# S7CAS-PLEIADES-CARTE-MERE_Pxx_FPGA_bank3.net
KiCad netlist of a schematic drawn in Altium Designer
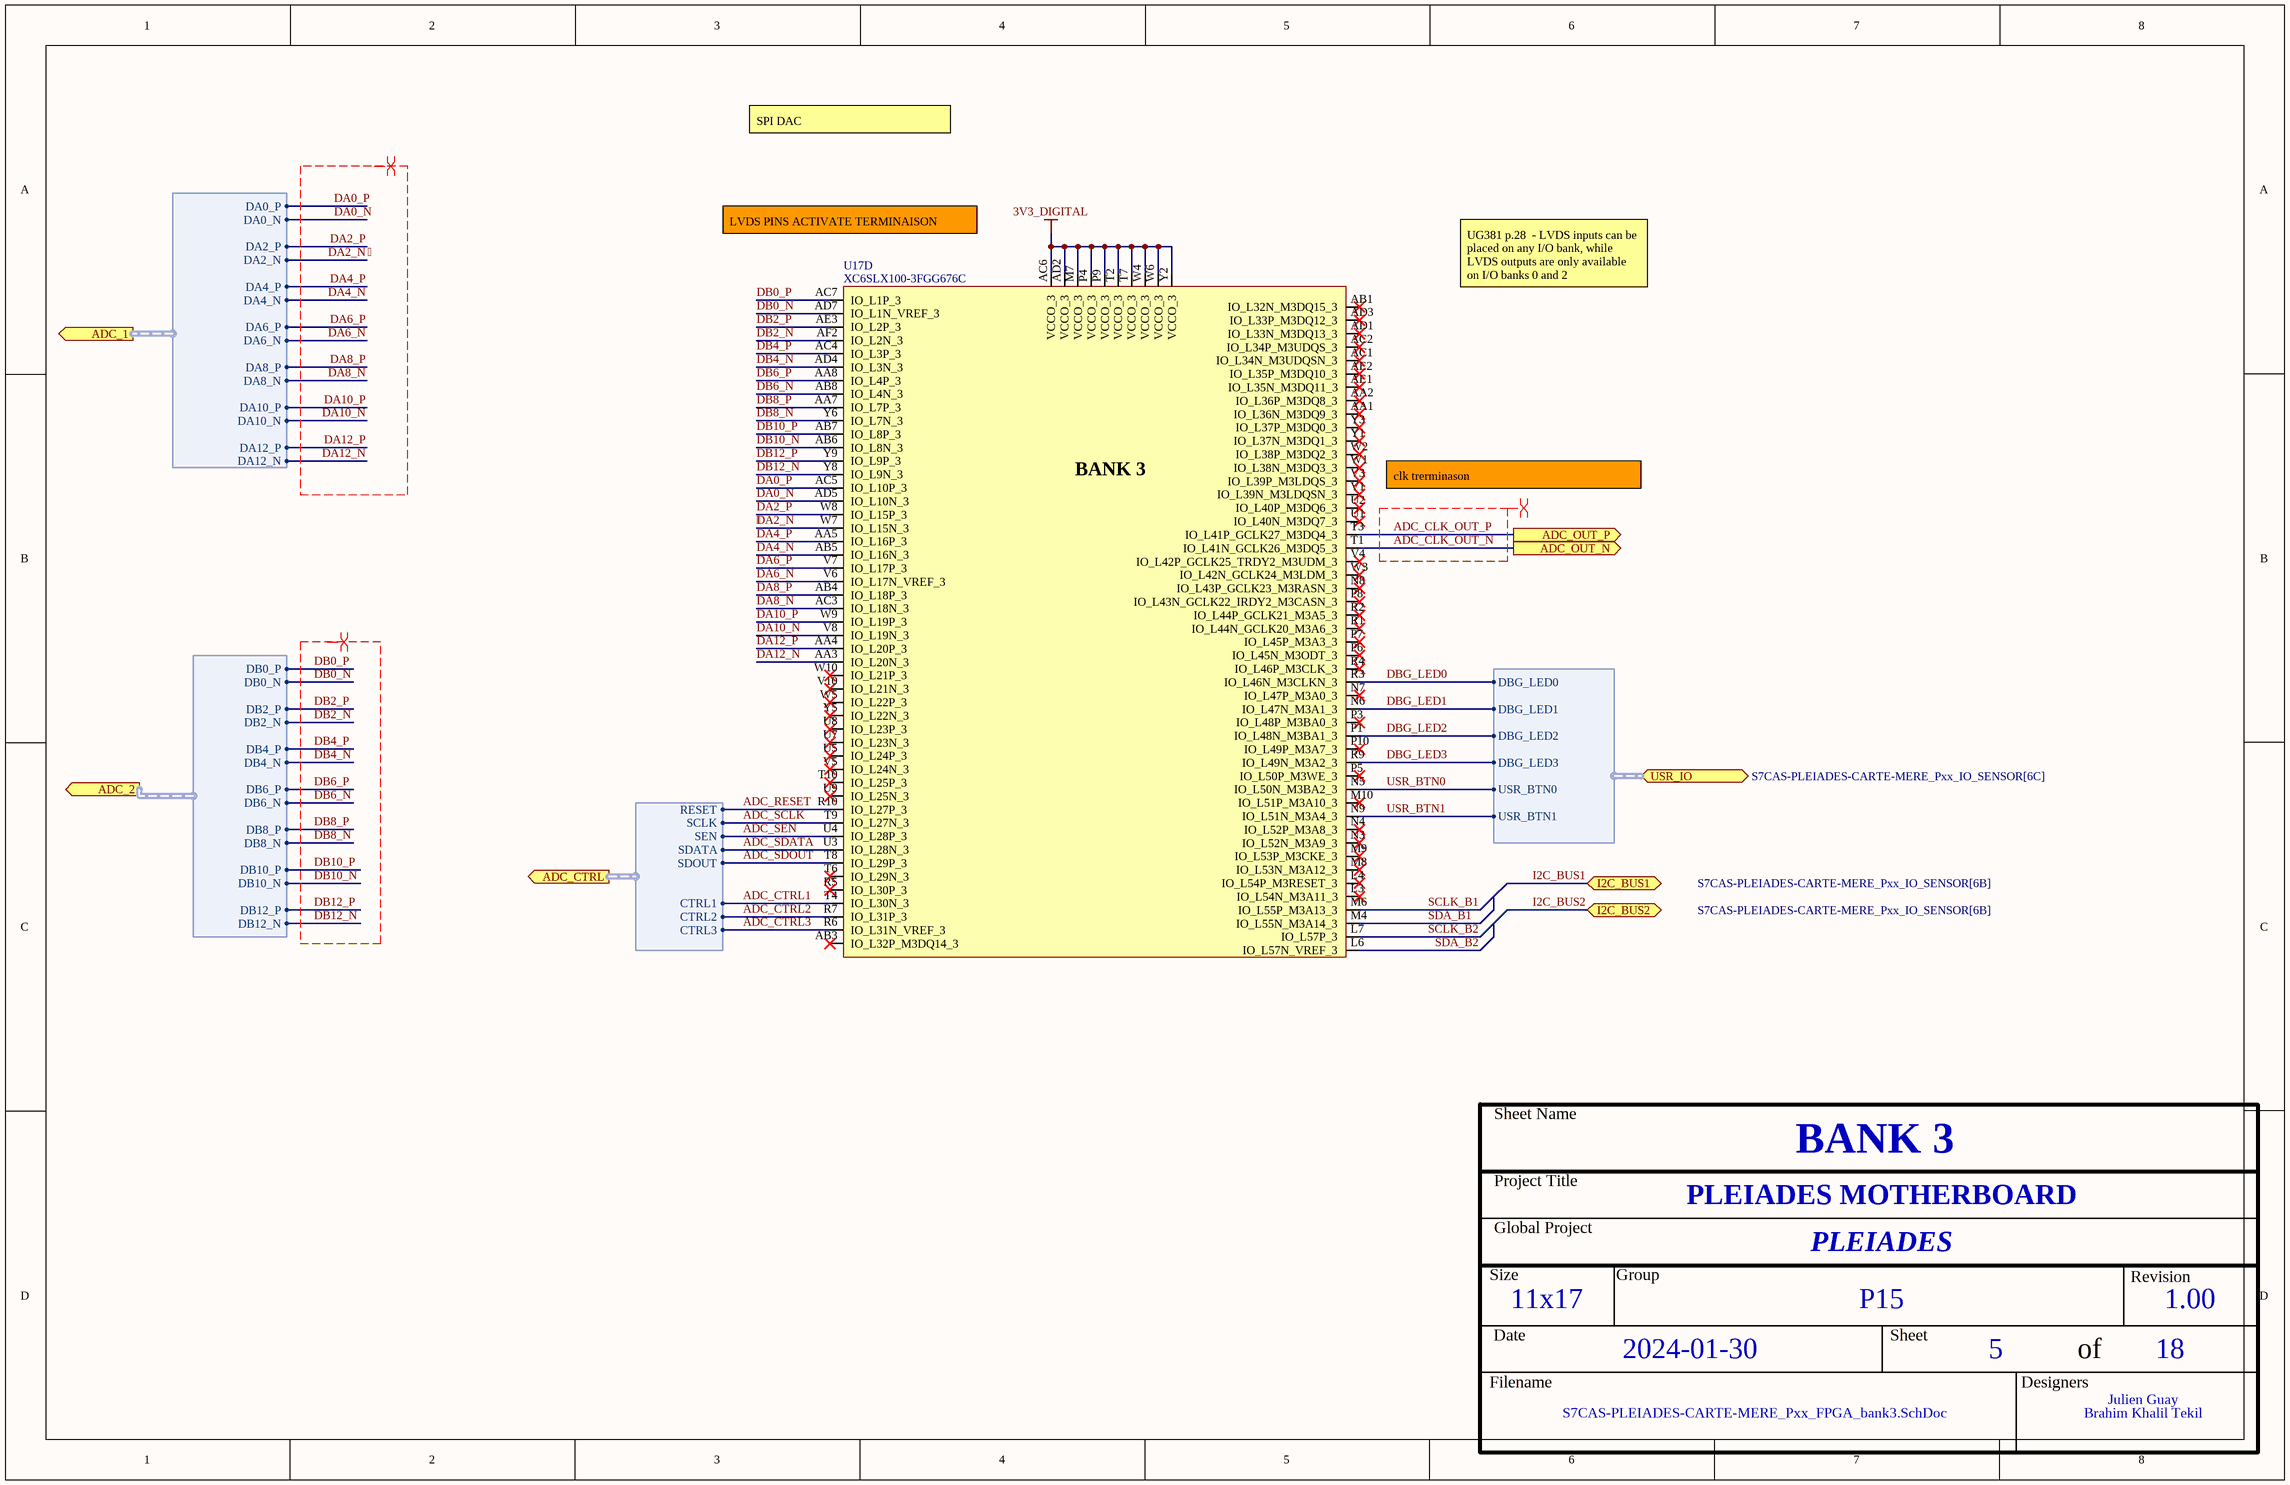
[diagram p0: S7CAS-PLEIADES-CARTE-MERE_Pxx_FPGA_bank3.SchDoc]

(export (version "E")
  (design (tool "Eeschema 10.0.6"))
  (components
    (comp (ref "U17")
      (value "XC6SLX100-3FGG676C")
      (footprint "FPGA_XILINX_FGG676")
      (description "FPGA - XILINX SPARTAN 6 480 I/O - BGA-676")
      (fields
        (field (name "VOLTAGE") "1.14 V ~ 1.26 V")
        (field (name "MFG") "Xilinx")
        (field (name "CREATEDBY") "Jonathan Bouchard")
      )
      (libsource (lib "S7CAS_LIB2023") (part "FPGA_XC6SLX100-3FGG676C"))
    )
  )
  (nets
    (net (code "7") (name "/") (class "Default")
      (node (ref "U17") (pin "W7") (pinfunction "IO_L15N_3_W7") (pintype "passive"))
    )
    (net (code "8") (name "/ADC_CLK_OUT_N") (class "Default")
      (node (ref "U17") (pin "T1") (pinfunction "IO_L41N_GCLK26_M3DQ5_3_T1") (pintype "passive"))
    )
    (net (code "9") (name "/ADC_CLK_OUT_P") (class "Default")
      (node (ref "U17") (pin "T3") (pinfunction "IO_L41P_GCLK27_M3DQ4_3_T3") (pintype "passive"))
    )
    (net (code "10") (name "/ADC_CTRL1") (class "Default")
      (node (ref "U17") (pin "T4") (pinfunction "IO_L30N_3_T4") (pintype "passive"))
    )
    (net (code "11") (name "/ADC_CTRL2") (class "Default")
      (node (ref "U17") (pin "R7") (pinfunction "IO_L31P_3_R7") (pintype "passive"))
    )
    (net (code "12") (name "/ADC_CTRL3") (class "Default")
      (node (ref "U17") (pin "R6") (pinfunction "IO_L31N_VREF_3_R6") (pintype "passive"))
    )
    (net (code "13") (name "/ADC_RESET") (class "Default")
      (node (ref "U17") (pin "R10") (pinfunction "IO_L27P_3_R10") (pintype "passive"))
    )
    (net (code "14") (name "/ADC_SCLK") (class "Default")
      (node (ref "U17") (pin "T9") (pinfunction "IO_L27N_3_T9") (pintype "passive"))
    )
    (net (code "15") (name "/ADC_SDATA") (class "Default")
      (node (ref "U17") (pin "U3") (pinfunction "IO_L28N_3_U3") (pintype "passive"))
    )
    (net (code "16") (name "/ADC_SDOUT") (class "Default")
      (node (ref "U17") (pin "T8") (pinfunction "IO_L29P_3_T8") (pintype "passive"))
    )
    (net (code "17") (name "/ADC_SEN") (class "Default")
      (node (ref "U17") (pin "U4") (pinfunction "IO_L28P_3_U4") (pintype "passive"))
    )
    (net (code "18") (name "/DA0_N") (class "Default")
      (node (ref "U17") (pin "AD5") (pinfunction "IO_L10N_3_AD5") (pintype "passive"))
    )
    (net (code "19") (name "/DA0_P") (class "Default")
      (node (ref "U17") (pin "AC5") (pinfunction "IO_L10P_3_AC5") (pintype "passive"))
    )
    (net (code "20") (name "/DA2_P") (class "Default")
      (node (ref "U17") (pin "W8") (pinfunction "IO_L15P_3_W8") (pintype "passive"))
    )
    (net (code "21") (name "/DA4_N") (class "Default")
      (node (ref "U17") (pin "AB5") (pinfunction "IO_L16N_3_AB5") (pintype "passive"))
    )
    (net (code "22") (name "/DA4_P") (class "Default")
      (node (ref "U17") (pin "AA5") (pinfunction "IO_L16P_3_AA5") (pintype "passive"))
    )
    (net (code "23") (name "/DA6_N") (class "Default")
      (node (ref "U17") (pin "V6") (pinfunction "IO_L17N_VREF_3_V6") (pintype "passive"))
    )
    (net (code "24") (name "/DA6_P") (class "Default")
      (node (ref "U17") (pin "V7") (pinfunction "IO_L17P_3_V7") (pintype "passive"))
    )
    (net (code "25") (name "/DA8_N") (class "Default")
      (node (ref "U17") (pin "AC3") (pinfunction "IO_L18N_3_AC3") (pintype "passive"))
    )
    (net (code "26") (name "/DA8_P") (class "Default")
      (node (ref "U17") (pin "AB4") (pinfunction "IO_L18P_3_AB4") (pintype "passive"))
    )
    (net (code "27") (name "/DA10_N") (class "Default")
      (node (ref "U17") (pin "V8") (pinfunction "IO_L19N_3_V8") (pintype "passive"))
    )
    (net (code "28") (name "/DA10_P") (class "Default")
      (node (ref "U17") (pin "W9") (pinfunction "IO_L19P_3_W9") (pintype "passive"))
    )
    (net (code "29") (name "/DA12_N") (class "Default")
      (node (ref "U17") (pin "AA3") (pinfunction "IO_L20N_3_AA3") (pintype "passive"))
    )
    (net (code "30") (name "/DA12_P") (class "Default")
      (node (ref "U17") (pin "AA4") (pinfunction "IO_L20P_3_AA4") (pintype "passive"))
    )
    (net (code "31") (name "/DB0_N") (class "Default")
      (node (ref "U17") (pin "AD7") (pinfunction "IO_L1N_VREF_3_AD7") (pintype "passive"))
    )
    (net (code "32") (name "/DB0_P") (class "Default")
      (node (ref "U17") (pin "AC7") (pinfunction "IO_L1P_3_AC7") (pintype "passive"))
    )
    (net (code "33") (name "/DB2_N") (class "Default")
      (node (ref "U17") (pin "AF2") (pinfunction "IO_L2N_3_AF2") (pintype "passive"))
    )
    (net (code "34") (name "/DB2_P") (class "Default")
      (node (ref "U17") (pin "AE3") (pinfunction "IO_L2P_3_AE3") (pintype "passive"))
    )
    (net (code "35") (name "/DB4_N") (class "Default")
      (node (ref "U17") (pin "AD4") (pinfunction "IO_L3N_3_AD4") (pintype "passive"))
    )
    (net (code "36") (name "/DB4_P") (class "Default")
      (node (ref "U17") (pin "AC4") (pinfunction "IO_L3P_3_AC4") (pintype "passive"))
    )
    (net (code "37") (name "/DB6_N") (class "Default")
      (node (ref "U17") (pin "AB8") (pinfunction "IO_L4N_3_AB8") (pintype "passive"))
    )
    (net (code "38") (name "/DB6_P") (class "Default")
      (node (ref "U17") (pin "AA8") (pinfunction "IO_L4P_3_AA8") (pintype "passive"))
    )
    (net (code "39") (name "/DB8_N") (class "Default")
      (node (ref "U17") (pin "Y6") (pinfunction "IO_L7N_3_Y6") (pintype "passive"))
    )
    (net (code "40") (name "/DB8_P") (class "Default")
      (node (ref "U17") (pin "AA7") (pinfunction "IO_L7P_3_AA7") (pintype "passive"))
    )
    (net (code "41") (name "/DB10_N") (class "Default")
      (node (ref "U17") (pin "AB6") (pinfunction "IO_L8N_3_AB6") (pintype "passive"))
    )
    (net (code "42") (name "/DB10_P") (class "Default")
      (node (ref "U17") (pin "AB7") (pinfunction "IO_L8P_3_AB7") (pintype "passive"))
    )
    (net (code "43") (name "/DB12_N") (class "Default")
      (node (ref "U17") (pin "Y8") (pinfunction "IO_L9N_3_Y8") (pintype "passive"))
    )
    (net (code "44") (name "/DB12_P") (class "Default")
      (node (ref "U17") (pin "Y9") (pinfunction "IO_L9P_3_Y9") (pintype "passive"))
    )
    (net (code "45") (name "/DBG_LED0") (class "Default")
      (node (ref "U17") (pin "R3") (pinfunction "IO_L46N_M3CLKN_3_R3") (pintype "passive"))
    )
    (net (code "46") (name "/DBG_LED1") (class "Default")
      (node (ref "U17") (pin "N6") (pinfunction "IO_L47N_M3A1_3_N6") (pintype "passive"))
    )
    (net (code "47") (name "/DBG_LED2") (class "Default")
      (node (ref "U17") (pin "P1") (pinfunction "IO_L48N_M3BA1_3_P1") (pintype "passive"))
    )
    (net (code "48") (name "/DBG_LED3") (class "Default")
      (node (ref "U17") (pin "R9") (pinfunction "IO_L49N_M3A2_3_R9") (pintype "passive"))
    )
    (net (code "49") (name "/SCLK_B1") (class "Default")
      (node (ref "U17") (pin "M6") (pinfunction "IO_L55P_M3A13_3_M6") (pintype "passive"))
    )
    (net (code "50") (name "/SCLK_B2") (class "Default")
      (node (ref "U17") (pin "L7") (pinfunction "IO_L57P_3_L7") (pintype "passive"))
    )
    (net (code "51") (name "/SDA_B1") (class "Default")
      (node (ref "U17") (pin "M4") (pinfunction "IO_L55N_M3A14_3_M4") (pintype "passive"))
    )
    (net (code "52") (name "/SDA_B2") (class "Default")
      (node (ref "U17") (pin "L6") (pinfunction "IO_L57N_VREF_3_L6") (pintype "passive"))
    )
    (net (code "53") (name "/USR_BTN0") (class "Default")
      (node (ref "U17") (pin "N5") (pinfunction "IO_L50N_M3BA2_3_N5") (pintype "passive"))
    )
    (net (code "54") (name "/USR_BTN1") (class "Default")
      (node (ref "U17") (pin "N9") (pinfunction "IO_L51N_M3A4_3_N9") (pintype "passive"))
    )
    (net (code "61") (name "3V3_DIGITAL") (class "Default")
      (node (ref "U17") (pin "AC6") (pinfunction "VCCO_3_AC6") (pintype "passive"))
      (node (ref "U17") (pin "AD2") (pinfunction "VCCO_3_AD2") (pintype "passive"))
      (node (ref "U17") (pin "M7") (pinfunction "VCCO_3_M7") (pintype "passive"))
      (node (ref "U17") (pin "P4") (pinfunction "VCCO_3_P4") (pintype "passive"))
      (node (ref "U17") (pin "P9") (pinfunction "VCCO_3_P9") (pintype "passive"))
      (node (ref "U17") (pin "T2") (pinfunction "VCCO_3_T2") (pintype "passive"))
      (node (ref "U17") (pin "T7") (pinfunction "VCCO_3_T7") (pintype "passive"))
      (node (ref "U17") (pin "W4") (pinfunction "VCCO_3_W4") (pintype "passive"))
      (node (ref "U17") (pin "W6") (pinfunction "VCCO_3_W6") (pintype "passive"))
      (node (ref "U17") (pin "Y2") (pinfunction "VCCO_3_Y2") (pintype "passive"))
    )
    (net (code "62") (name "unconnected-(U17D-IO_L21N_3-PadV10)") (class "Default")
      (node (ref "U17") (pin "V10") (pinfunction "IO_L21N_3_V10") (pintype "passive+no_connect"))
    )
    (net (code "63") (name "unconnected-(U17D-IO_L21P_3-PadW10)") (class "Default")
      (node (ref "U17") (pin "W10") (pinfunction "IO_L21P_3_W10") (pintype "passive+no_connect"))
    )
    (net (code "64") (name "unconnected-(U17D-IO_L22N_3-PadY5)") (class "Default")
      (node (ref "U17") (pin "Y5") (pinfunction "IO_L22N_3_Y5") (pintype "passive+no_connect"))
    )
    (net (code "65") (name "unconnected-(U17D-IO_L22P_3-PadW5)") (class "Default")
      (node (ref "U17") (pin "W5") (pinfunction "IO_L22P_3_W5") (pintype "passive+no_connect"))
    )
    (net (code "66") (name "unconnected-(U17D-IO_L23N_3-PadU7)") (class "Default")
      (node (ref "U17") (pin "U7") (pinfunction "IO_L23N_3_U7") (pintype "passive+no_connect"))
    )
    (net (code "67") (name "unconnected-(U17D-IO_L23P_3-PadU8)") (class "Default")
      (node (ref "U17") (pin "U8") (pinfunction "IO_L23P_3_U8") (pintype "passive+no_connect"))
    )
    (net (code "68") (name "unconnected-(U17D-IO_L24N_3-PadV5)") (class "Default")
      (node (ref "U17") (pin "V5") (pinfunction "IO_L24N_3_V5") (pintype "passive+no_connect"))
    )
    (net (code "69") (name "unconnected-(U17D-IO_L24P_3-PadU5)") (class "Default")
      (node (ref "U17") (pin "U5") (pinfunction "IO_L24P_3_U5") (pintype "passive+no_connect"))
    )
    (net (code "70") (name "unconnected-(U17D-IO_L25N_3-PadU9)") (class "Default")
      (node (ref "U17") (pin "U9") (pinfunction "IO_L25N_3_U9") (pintype "passive+no_connect"))
    )
    (net (code "71") (name "unconnected-(U17D-IO_L25P_3-PadT10)") (class "Default")
      (node (ref "U17") (pin "T10") (pinfunction "IO_L25P_3_T10") (pintype "passive+no_connect"))
    )
    (net (code "72") (name "unconnected-(U17D-IO_L29N_3-PadT6)") (class "Default")
      (node (ref "U17") (pin "T6") (pinfunction "IO_L29N_3_T6") (pintype "passive+no_connect"))
    )
    (net (code "73") (name "unconnected-(U17D-IO_L30P_3-PadR5)") (class "Default")
      (node (ref "U17") (pin "R5") (pinfunction "IO_L30P_3_R5") (pintype "passive+no_connect"))
    )
    (net (code "74") (name "unconnected-(U17D-IO_L32N_M3DQ15_3-PadAB1)") (class "Default")
      (node (ref "U17") (pin "AB1") (pinfunction "IO_L32N_M3DQ15_3_AB1") (pintype "passive+no_connect"))
    )
    (net (code "75") (name "unconnected-(U17D-IO_L32P_M3DQ14_3-PadAB3)") (class "Default")
      (node (ref "U17") (pin "AB3") (pinfunction "IO_L32P_M3DQ14_3_AB3") (pintype "passive+no_connect"))
    )
    (net (code "76") (name "unconnected-(U17D-IO_L33N_M3DQ13_3-PadAD1)") (class "Default")
      (node (ref "U17") (pin "AD1") (pinfunction "IO_L33N_M3DQ13_3_AD1") (pintype "passive+no_connect"))
    )
    (net (code "77") (name "unconnected-(U17D-IO_L33P_M3DQ12_3-PadAD3)") (class "Default")
      (node (ref "U17") (pin "AD3") (pinfunction "IO_L33P_M3DQ12_3_AD3") (pintype "passive+no_connect"))
    )
    (net (code "78") (name "unconnected-(U17D-IO_L34N_M3UDQSN_3-PadAC1)") (class "Default")
      (node (ref "U17") (pin "AC1") (pinfunction "IO_L34N_M3UDQSN_3_AC1") (pintype "passive+no_connect"))
    )
    (net (code "79") (name "unconnected-(U17D-IO_L34P_M3UDQS_3-PadAC2)") (class "Default")
      (node (ref "U17") (pin "AC2") (pinfunction "IO_L34P_M3UDQS_3_AC2") (pintype "passive+no_connect"))
    )
    (net (code "80") (name "unconnected-(U17D-IO_L35N_M3DQ11_3-PadAE1)") (class "Default")
      (node (ref "U17") (pin "AE1") (pinfunction "IO_L35N_M3DQ11_3_AE1") (pintype "passive+no_connect"))
    )
    (net (code "81") (name "unconnected-(U17D-IO_L35P_M3DQ10_3-PadAE2)") (class "Default")
      (node (ref "U17") (pin "AE2") (pinfunction "IO_L35P_M3DQ10_3_AE2") (pintype "passive+no_connect"))
    )
    (net (code "82") (name "unconnected-(U17D-IO_L36N_M3DQ9_3-PadAA1)") (class "Default")
      (node (ref "U17") (pin "AA1") (pinfunction "IO_L36N_M3DQ9_3_AA1") (pintype "passive+no_connect"))
    )
    (net (code "83") (name "unconnected-(U17D-IO_L36P_M3DQ8_3-PadAA2)") (class "Default")
      (node (ref "U17") (pin "AA2") (pinfunction "IO_L36P_M3DQ8_3_AA2") (pintype "passive+no_connect"))
    )
    (net (code "84") (name "unconnected-(U17D-IO_L37N_M3DQ1_3-PadY1)") (class "Default")
      (node (ref "U17") (pin "Y1") (pinfunction "IO_L37N_M3DQ1_3_Y1") (pintype "passive+no_connect"))
    )
    (net (code "85") (name "unconnected-(U17D-IO_L37P_M3DQ0_3-PadY3)") (class "Default")
      (node (ref "U17") (pin "Y3") (pinfunction "IO_L37P_M3DQ0_3_Y3") (pintype "passive+no_connect"))
    )
    (net (code "86") (name "unconnected-(U17D-IO_L38N_M3DQ3_3-PadW1)") (class "Default")
      (node (ref "U17") (pin "W1") (pinfunction "IO_L38N_M3DQ3_3_W1") (pintype "passive+no_connect"))
    )
    (net (code "87") (name "unconnected-(U17D-IO_L38P_M3DQ2_3-PadW2)") (class "Default")
      (node (ref "U17") (pin "W2") (pinfunction "IO_L38P_M3DQ2_3_W2") (pintype "passive+no_connect"))
    )
    (net (code "88") (name "unconnected-(U17D-IO_L39N_M3LDQSN_3-PadV1)") (class "Default")
      (node (ref "U17") (pin "V1") (pinfunction "IO_L39N_M3LDQSN_3_V1") (pintype "passive+no_connect"))
    )
    (net (code "89") (name "unconnected-(U17D-IO_L39P_M3LDQS_3-PadV3)") (class "Default")
      (node (ref "U17") (pin "V3") (pinfunction "IO_L39P_M3LDQS_3_V3") (pintype "passive+no_connect"))
    )
    (net (code "90") (name "unconnected-(U17D-IO_L40N_M3DQ7_3-PadU1)") (class "Default")
      (node (ref "U17") (pin "U1") (pinfunction "IO_L40N_M3DQ7_3_U1") (pintype "passive+no_connect"))
    )
    (net (code "91") (name "unconnected-(U17D-IO_L40P_M3DQ6_3-PadU2)") (class "Default")
      (node (ref "U17") (pin "U2") (pinfunction "IO_L40P_M3DQ6_3_U2") (pintype "passive+no_connect"))
    )
    (net (code "92") (name "unconnected-(U17D-IO_L42N_GCLK24_M3LDM_3-PadW3)") (class "Default")
      (node (ref "U17") (pin "W3") (pinfunction "IO_L42N_GCLK24_M3LDM_3_W3") (pintype "passive+no_connect"))
    )
    (net (code "93") (name "unconnected-(U17D-IO_L42P_GCLK25_TRDY2_M3UDM_3-PadV4)") (class "Default")
      (node (ref "U17") (pin "V4") (pinfunction "IO_L42P_GCLK25_TRDY2_M3UDM_3_V4") (pintype "passive+no_connect"))
    )
    (net (code "94") (name "unconnected-(U17D-IO_L43N_GCLK22_IRDY2_M3CASN_3-PadP8)") (class "Default")
      (node (ref "U17") (pin "P8") (pinfunction "IO_L43N_GCLK22_IRDY2_M3CASN_3_P8") (pintype "passive+no_connect"))
    )
    (net (code "95") (name "unconnected-(U17D-IO_L43P_GCLK23_M3RASN_3-PadN8)") (class "Default")
      (node (ref "U17") (pin "N8") (pinfunction "IO_L43P_GCLK23_M3RASN_3_N8") (pintype "passive+no_connect"))
    )
    (net (code "96") (name "unconnected-(U17D-IO_L44N_GCLK20_M3A6_3-PadR1)") (class "Default")
      (node (ref "U17") (pin "R1") (pinfunction "IO_L44N_GCLK20_M3A6_3_R1") (pintype "passive+no_connect"))
    )
    (net (code "97") (name "unconnected-(U17D-IO_L44P_GCLK21_M3A5_3-PadR2)") (class "Default")
      (node (ref "U17") (pin "R2") (pinfunction "IO_L44P_GCLK21_M3A5_3_R2") (pintype "passive+no_connect"))
    )
    (net (code "98") (name "unconnected-(U17D-IO_L45N_M3ODT_3-PadP6)") (class "Default")
      (node (ref "U17") (pin "P6") (pinfunction "IO_L45N_M3ODT_3_P6") (pintype "passive+no_connect"))
    )
    (net (code "99") (name "unconnected-(U17D-IO_L45P_M3A3_3-PadP7)") (class "Default")
      (node (ref "U17") (pin "P7") (pinfunction "IO_L45P_M3A3_3_P7") (pintype "passive+no_connect"))
    )
    (net (code "100") (name "unconnected-(U17D-IO_L46P_M3CLK_3-PadR4)") (class "Default")
      (node (ref "U17") (pin "R4") (pinfunction "IO_L46P_M3CLK_3_R4") (pintype "passive+no_connect"))
    )
    (net (code "101") (name "unconnected-(U17D-IO_L47P_M3A0_3-PadN7)") (class "Default")
      (node (ref "U17") (pin "N7") (pinfunction "IO_L47P_M3A0_3_N7") (pintype "passive+no_connect"))
    )
    (net (code "102") (name "unconnected-(U17D-IO_L48P_M3BA0_3-PadP3)") (class "Default")
      (node (ref "U17") (pin "P3") (pinfunction "IO_L48P_M3BA0_3_P3") (pintype "passive+no_connect"))
    )
    (net (code "103") (name "unconnected-(U17D-IO_L49P_M3A7_3-PadP10)") (class "Default")
      (node (ref "U17") (pin "P10") (pinfunction "IO_L49P_M3A7_3_P10") (pintype "passive+no_connect"))
    )
    (net (code "104") (name "unconnected-(U17D-IO_L50P_M3WE_3-PadP5)") (class "Default")
      (node (ref "U17") (pin "P5") (pinfunction "IO_L50P_M3WE_3_P5") (pintype "passive+no_connect"))
    )
    (net (code "105") (name "unconnected-(U17D-IO_L51P_M3A10_3-PadM10)") (class "Default")
      (node (ref "U17") (pin "M10") (pinfunction "IO_L51P_M3A10_3_M10") (pintype "passive+no_connect"))
    )
    (net (code "106") (name "unconnected-(U17D-IO_L52N_M3A9_3-PadN3)") (class "Default")
      (node (ref "U17") (pin "N3") (pinfunction "IO_L52N_M3A9_3_N3") (pintype "passive+no_connect"))
    )
    (net (code "107") (name "unconnected-(U17D-IO_L52P_M3A8_3-PadN4)") (class "Default")
      (node (ref "U17") (pin "N4") (pinfunction "IO_L52P_M3A8_3_N4") (pintype "passive+no_connect"))
    )
    (net (code "108") (name "unconnected-(U17D-IO_L53N_M3A12_3-PadM8)") (class "Default")
      (node (ref "U17") (pin "M8") (pinfunction "IO_L53N_M3A12_3_M8") (pintype "passive+no_connect"))
    )
    (net (code "109") (name "unconnected-(U17D-IO_L53P_M3CKE_3-PadM9)") (class "Default")
      (node (ref "U17") (pin "M9") (pinfunction "IO_L53P_M3CKE_3_M9") (pintype "passive+no_connect"))
    )
    (net (code "110") (name "unconnected-(U17D-IO_L54N_M3A11_3-PadL3)") (class "Default")
      (node (ref "U17") (pin "L3") (pinfunction "IO_L54N_M3A11_3_L3") (pintype "passive+no_connect"))
    )
    (net (code "111") (name "unconnected-(U17D-IO_L54P_M3RESET_3-PadL4)") (class "Default")
      (node (ref "U17") (pin "L4") (pinfunction "IO_L54P_M3RESET_3_L4") (pintype "passive+no_connect"))
    )
  )
)
